# Power2.net
KiCad netlist of a schematic drawn in Altium Designer
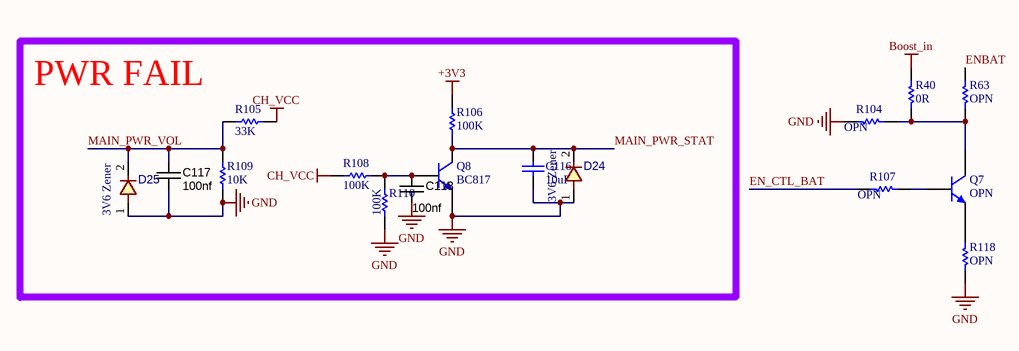
[diagram p0: Power2.SchDoc]

(export (version "E")
  (design (tool "Eeschema 10.0.6"))
  (components
    (comp (ref "C116")
      (value "10uF")
      (footprint "CAPC3413X12N")
      (description "CAP 0805")
      (fields (field (name "DESIGNER") "Abbas Basereh"))
      (libsource (lib "2017AbbasBasereh9365731239 -ver1") (part "CAP SMD 0805"))
    )
    (comp (ref "C117")
      (value "100nf")
      (footprint "CAPC1608X90N")
      (description "Capacitor SMD Cer 100nF 10% 50V X7R 0603")
      (fields (field (name "TOLERANCE") "±10%"))
      (libsource (lib "altium-import") (part "root_0_CAPC_100n_0603_X7R_50V_10%_"))
    )
    (comp (ref "C118")
      (value "100nf")
      (footprint "CAPC1608X90N")
      (description "Capacitor SMD Cer 100nF 10% 50V X7R 0603")
      (fields (field (name "TOLERANCE") "±10%"))
      (libsource (lib "altium-import") (part "root_0_CAPC_100n_0603_X7R_50V_10%_"))
    )
    (comp (ref "D24")
      (value "3V6 Zener")
      (footprint "D_SOD80")
      (description "DIODE, FAST SWTICHING, 0.3A, 0.5W")
      (fields (field (name "Comment") "5Z1"))
      (libsource (lib "Diode") (part "1N4148 SMD"))
    )
    (comp (ref "D25")
      (value "3V6 Zener")
      (footprint "D_SOD80")
      (description "DIODE, FAST SWTICHING, 0.3A, 0.5W")
      (fields (field (name "Comment") "5Z1"))
      (libsource (lib "Diode") (part "1N4148 SMD"))
    )
    (comp (ref "Q7")
      (value "OPN")
      (footprint "SOT23_N")
      (description "NPN Silicon Epitaxial Planar Transistor")
      (fields (field (name "PUBLISHER") "Abbas Basereh"))
      (libsource (lib "2017AbbasBasereh9365731239 -ver1") (part "C945"))
    )
    (comp (ref "Q8")
      (value "BC817")
      (footprint "SOT23_N")
      (description "NPN Silicon Epitaxial Planar Transistor")
      (fields (field (name "PUBLISHER") "Abbas Basereh"))
      (libsource (lib "altium-import") (part "root_0_C945_"))
    )
    (comp (ref "R40")
      (value "0R")
      (footprint "R0603")
      (description "Resistor SMD 0603")
      (libsource (lib "Resistor") (part "Resistor SMD 0603"))
    )
    (comp (ref "R63")
      (value "OPN")
      (footprint "R0603")
      (description "Resistor SMD 0603")
      (libsource (lib "Resistor") (part "Resistor SMD 0603"))
    )
    (comp (ref "R104")
      (value "OPN")
      (footprint "R0603")
      (description "Resistor SMD 0603")
      (libsource (lib "Resistor") (part "Resistor SMD 0603"))
    )
    (comp (ref "R105")
      (value "33K")
      (footprint "Resistor_SMD_0603 (1608)")
      (description "Resistor 0603")
      (fields (field (name "PUBLISHER") "Seyed Razi Vesali") (field (name "EMAIL") "razi.vesali@gmail.com"))
      (libsource (lib "resistors") (part "Resistor"))
    )
    (comp (ref "R106")
      (value "100K")
      (footprint "Resistor_SMD_0603 (1608)")
      (description "Resistor 0603")
      (fields (field (name "PUBLISHER") "Seyed Razi Vesali") (field (name "EMAIL") "razi.vesali@gmail.com"))
      (libsource (lib "resistors") (part "Resistor"))
    )
    (comp (ref "R107")
      (value "OPN")
      (footprint "R0603")
      (description "Resistor SMD 0603")
      (libsource (lib "Resistor") (part "Resistor SMD 0603"))
    )
    (comp (ref "R108")
      (value "100K")
      (footprint "Resistor_SMD_0603 (1608)")
      (description "Resistor 0603")
      (fields (field (name "PUBLISHER") "Seyed Razi Vesali") (field (name "EMAIL") "razi.vesali@gmail.com"))
      (libsource (lib "resistors") (part "Resistor"))
    )
    (comp (ref "R109")
      (value "10K")
      (footprint "Resistor_SMD_0603 (1608)")
      (description "Resistor0603")
      (fields (field (name "PUBLISHER") "Seyed Razi Vesali") (field (name "EMAIL") "razi.vesali@gmail.com"))
      (libsource (lib "resistors") (part "Resistor"))
    )
    (comp (ref "R110")
      (value "100K")
      (footprint "Resistor_SMD_0603 (1608)")
      (description "Resistor 0603")
      (fields (field (name "PUBLISHER") "Seyed Razi Vesali") (field (name "EMAIL") "razi.vesali@gmail.com"))
      (libsource (lib "resistors") (part "Resistor"))
    )
    (comp (ref "R118")
      (value "OPN")
      (footprint "R0603")
      (description "Resistor SMD 0603")
      (libsource (lib "Resistor") (part "Resistor SMD 0603"))
    )
  )
  (nets
    (net (code "1") (name "+3V3") (class "Default")
      (node (ref "R106") (pin "1") (pinfunction "1_1") (pintype "passive"))
    )
    (net (code "2") (name "/ENBAT") (class "Default")
      (node (ref "R63") (pin "1") (pinfunction "1_1") (pintype "passive"))
    )
    (net (code "3") (name "/EN_CTL_BAT") (class "Default")
      (node (ref "R107") (pin "2") (pinfunction "2_2") (pintype "passive"))
    )
    (net (code "4") (name "/MAIN_PWR_STAT") (class "Default")
      (node (ref "C116") (pin "2") (pinfunction "2_2") (pintype "passive"))
      (node (ref "D24") (pin "2") (pinfunction "2_2") (pintype "passive"))
      (node (ref "Q8") (pin "3") (pinfunction "C_3") (pintype "passive"))
      (node (ref "R106") (pin "2") (pinfunction "2_2") (pintype "passive"))
    )
    (net (code "5") (name "/MAIN_PWR_VOL") (class "Default")
      (node (ref "C117") (pin "1") (pintype "passive"))
      (node (ref "D25") (pin "2") (pinfunction "2_2") (pintype "passive"))
      (node (ref "R105") (pin "1") (pinfunction "1_1") (pintype "passive"))
      (node (ref "R109") (pin "2") (pinfunction "2_2") (pintype "passive"))
    )
    (net (code "6") (name "Boost_in") (class "Default")
      (node (ref "R40") (pin "1") (pinfunction "1_1") (pintype "passive"))
    )
    (net (code "7") (name "CH_VCC") (class "Default")
      (node (ref "R105") (pin "2") (pinfunction "2_2") (pintype "passive"))
      (node (ref "R108") (pin "1") (pinfunction "1_1") (pintype "passive"))
    )
    (net (code "8") (name "GND") (class "Default")
      (node (ref "C116") (pin "1") (pinfunction "1_1") (pintype "passive"))
      (node (ref "C117") (pin "2") (pintype "passive"))
      (node (ref "C118") (pin "2") (pintype "passive"))
      (node (ref "D24") (pin "1") (pinfunction "1_1") (pintype "passive"))
      (node (ref "D25") (pin "1") (pinfunction "1_1") (pintype "passive"))
      (node (ref "Q8") (pin "2") (pinfunction "E_2") (pintype "passive"))
      (node (ref "R104") (pin "2") (pinfunction "2_2") (pintype "passive"))
      (node (ref "R109") (pin "1") (pinfunction "1_1") (pintype "passive"))
      (node (ref "R110") (pin "1") (pinfunction "1_1") (pintype "passive"))
      (node (ref "R118") (pin "2") (pinfunction "2_2") (pintype "passive"))
    )
    (net (code "9") (name "Net-(Q7-B)") (class "Default")
      (node (ref "Q7") (pin "1") (pinfunction "B_1") (pintype "passive"))
      (node (ref "R107") (pin "1") (pinfunction "1_1") (pintype "passive"))
    )
    (net (code "10") (name "Net-(Q7-C)") (class "Default")
      (node (ref "Q7") (pin "3") (pinfunction "C_3") (pintype "passive"))
      (node (ref "R104") (pin "1") (pinfunction "1_1") (pintype "passive"))
      (node (ref "R40") (pin "2") (pinfunction "2_2") (pintype "passive"))
      (node (ref "R63") (pin "2") (pinfunction "2_2") (pintype "passive"))
    )
    (net (code "11") (name "Net-(Q7-E)") (class "Default")
      (node (ref "Q7") (pin "2") (pinfunction "E_2") (pintype "passive"))
      (node (ref "R118") (pin "1") (pinfunction "1_1") (pintype "passive"))
    )
    (net (code "12") (name "Net-(Q8-B)") (class "Default")
      (node (ref "C118") (pin "1") (pintype "passive"))
      (node (ref "Q8") (pin "1") (pinfunction "B_1") (pintype "passive"))
      (node (ref "R108") (pin "2") (pinfunction "2_2") (pintype "passive"))
      (node (ref "R110") (pin "2") (pinfunction "2_2") (pintype "passive"))
    )
  )
)
